# usb_host_eurorack.net
KiCad netlist of a schematic drawn in EAGLE
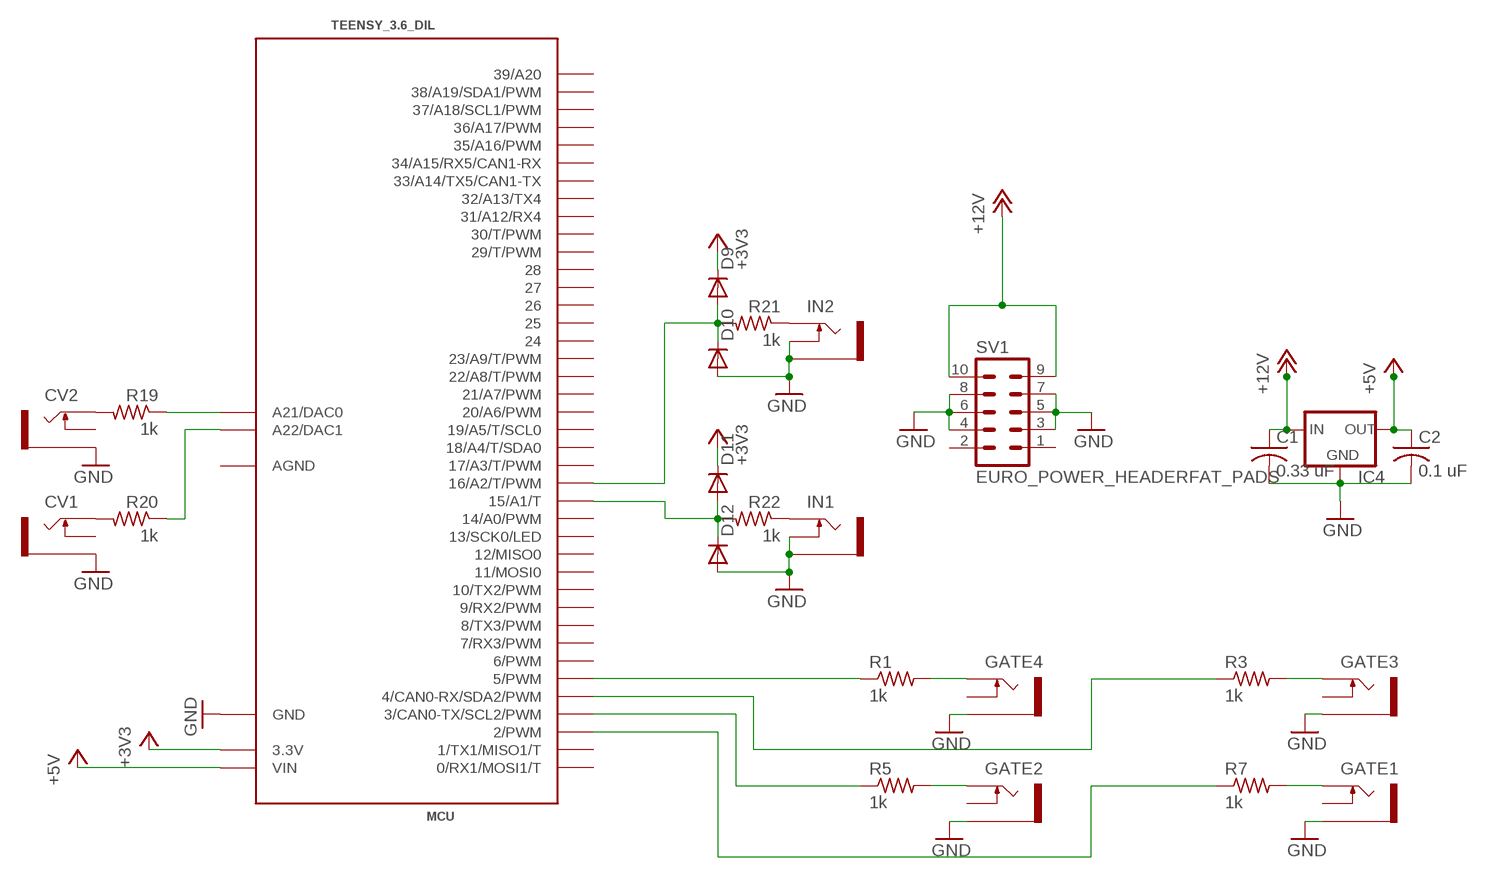
[diagram p0: schematic, sheet 1]

(export (version "E")
  (design (tool "Eeschema 10.0.6"))
  (components
    (comp (ref "C1")
      (value "0.33 uF")
      (footprint "eagle-import:C025-030X050")
      (libsource (lib "eagle-import") (part "C-US025-030X050"))
    )
    (comp (ref "C2")
      (value "0.1 uF")
      (footprint "eagle-import:C025-030X050")
      (libsource (lib "eagle-import") (part "C-US025-030X050"))
    )
    (comp (ref "CV1")
      (value "PJ302M")
      (footprint "eagle-import:PJ302M")
      (libsource (lib "eagle-import") (part "PJ302M"))
    )
    (comp (ref "CV2")
      (value "PJ302M")
      (footprint "eagle-import:PJ302M")
      (libsource (lib "eagle-import") (part "PJ302M"))
    )
    (comp (ref "D9")
      (value "SMALL_DIODEDO35-7")
      (footprint "eagle-import:DO35-7")
      (libsource (lib "eagle-import") (part "SMALL_DIODEDO35-7"))
    )
    (comp (ref "D10")
      (value "SMALL_DIODEDO35-7")
      (footprint "eagle-import:DO35-7")
      (libsource (lib "eagle-import") (part "SMALL_DIODEDO35-7"))
    )
    (comp (ref "D11")
      (value "SMALL_DIODEDO35-7")
      (footprint "eagle-import:DO35-7")
      (libsource (lib "eagle-import") (part "SMALL_DIODEDO35-7"))
    )
    (comp (ref "D12")
      (value "SMALL_DIODEDO35-7")
      (footprint "eagle-import:DO35-7")
      (libsource (lib "eagle-import") (part "SMALL_DIODEDO35-7"))
    )
    (comp (ref "GATE1")
      (value "PJ302M")
      (footprint "eagle-import:PJ302M")
      (libsource (lib "eagle-import") (part "PJ302M"))
    )
    (comp (ref "GATE2")
      (value "PJ302M")
      (footprint "eagle-import:PJ302M")
      (libsource (lib "eagle-import") (part "PJ302M"))
    )
    (comp (ref "GATE3")
      (value "PJ302M")
      (footprint "eagle-import:PJ302M")
      (libsource (lib "eagle-import") (part "PJ302M"))
    )
    (comp (ref "GATE4")
      (value "PJ302M")
      (footprint "eagle-import:PJ302M")
      (libsource (lib "eagle-import") (part "PJ302M"))
    )
    (comp (ref "IC4")
      (value "78XXL")
      (footprint "eagle-import:78XXL")
      (libsource (lib "eagle-import") (part "78XXL"))
    )
    (comp (ref "IN1")
      (value "PJ302M")
      (footprint "eagle-import:PJ302M")
      (libsource (lib "eagle-import") (part "PJ302M"))
    )
    (comp (ref "IN2")
      (value "PJ302M")
      (footprint "eagle-import:PJ302M")
      (libsource (lib "eagle-import") (part "PJ302M"))
    )
    (comp (ref "MCU")
      (value "TEENSY_3.6_DIL")
      (footprint "eagle-import:TEENSY_3.6_DIL")
      (libsource (lib "eagle-import") (part "TEENSY_3.6_DIL"))
    )
    (comp (ref "R1")
      (value "1k")
      (footprint "eagle-import:0207_10")
      (libsource (lib "eagle-import") (part "R-US_0207/10"))
    )
    (comp (ref "R3")
      (value "1k")
      (footprint "eagle-import:0207_10")
      (libsource (lib "eagle-import") (part "R-US_0207/10"))
    )
    (comp (ref "R5")
      (value "1k")
      (footprint "eagle-import:0207_10")
      (libsource (lib "eagle-import") (part "R-US_0207/10"))
    )
    (comp (ref "R7")
      (value "1k")
      (footprint "eagle-import:0207_10")
      (libsource (lib "eagle-import") (part "R-US_0207/10"))
    )
    (comp (ref "R19")
      (value "1k")
      (footprint "eagle-import:0207_10")
      (libsource (lib "eagle-import") (part "R-US_0207/10"))
    )
    (comp (ref "R20")
      (value "1k")
      (footprint "eagle-import:0207_10")
      (libsource (lib "eagle-import") (part "R-US_0207/10"))
    )
    (comp (ref "R21")
      (value "1k")
      (footprint "eagle-import:0207_10")
      (libsource (lib "eagle-import") (part "R-US_0207/10"))
    )
    (comp (ref "R22")
      (value "1k")
      (footprint "eagle-import:0207_10")
      (libsource (lib "eagle-import") (part "R-US_0207/10"))
    )
    (comp (ref "SV1")
      (value "EURO_POWER_HEADERFAT_PADS")
      (footprint "eagle-import:EURO_PWR_HEADER_FAT")
      (libsource (lib "eagle-import") (part "EURO_POWER_HEADERFAT_PADS"))
    )
  )
  (nets
    (net (code "1") (name "+3V3") (class "Default")
      (node (ref "D11") (pin "C") (pinfunction "C_C") (pintype "passive"))
      (node (ref "D9") (pin "C") (pinfunction "C_C") (pintype "passive"))
      (node (ref "MCU") (pin "3.3V") (pinfunction "3.3V_3.3V") (pintype "power_in"))
      (node (ref "MCU") (pin "3.3V3") (pinfunction "3.3V_3.3V3") (pintype "power_in"))
    )
    (net (code "2") (name "+5V") (class "Default")
      (node (ref "C2") (pin "1") (pinfunction "1_1") (pintype "passive"))
      (node (ref "IC4") (pin "OUT") (pinfunction "OUT_OUT") (pintype "passive"))
      (node (ref "MCU") (pin "VIN") (pinfunction "VIN_VIN") (pintype "power_in"))
    )
    (net (code "3") (name "+12V") (class "Default")
      (node (ref "C1") (pin "1") (pinfunction "1_1") (pintype "passive"))
      (node (ref "IC4") (pin "IN") (pinfunction "IN_IN") (pintype "input"))
      (node (ref "SV1") (pin "10") (pinfunction "10_10") (pintype "passive"))
      (node (ref "SV1") (pin "9") (pinfunction "9_9") (pintype "passive"))
    )
    (net (code "4") (name "/AGND") (class "Default")
      (node (ref "MCU") (pin "AGND") (pinfunction "AGND_AGND") (pintype "power_in"))
    )
    (net (code "5") (name "GND") (class "Default")
      (node (ref "C1") (pin "2") (pinfunction "2_2") (pintype "passive"))
      (node (ref "C2") (pin "2") (pinfunction "2_2") (pintype "passive"))
      (node (ref "CV1") (pin "GND") (pinfunction "SLEEVE_GND") (pintype "passive"))
      (node (ref "CV2") (pin "GND") (pinfunction "SLEEVE_GND") (pintype "passive"))
      (node (ref "D10") (pin "A") (pinfunction "A_A") (pintype "passive"))
      (node (ref "D12") (pin "A") (pinfunction "A_A") (pintype "passive"))
      (node (ref "GATE1") (pin "GND") (pinfunction "SLEEVE_GND") (pintype "passive"))
      (node (ref "GATE2") (pin "GND") (pinfunction "SLEEVE_GND") (pintype "passive"))
      (node (ref "GATE3") (pin "GND") (pinfunction "SLEEVE_GND") (pintype "passive"))
      (node (ref "GATE4") (pin "GND") (pinfunction "SLEEVE_GND") (pintype "passive"))
      (node (ref "IC4") (pin "GND") (pinfunction "GND_GND") (pintype "input"))
      (node (ref "IN1") (pin "GND") (pinfunction "SLEEVE_GND") (pintype "passive"))
      (node (ref "IN1") (pin "SW") (pinfunction "SWITCH_SW") (pintype "passive"))
      (node (ref "IN2") (pin "GND") (pinfunction "SLEEVE_GND") (pintype "passive"))
      (node (ref "IN2") (pin "SW") (pinfunction "SWITCH_SW") (pintype "passive"))
      (node (ref "MCU") (pin "GND") (pinfunction "GND_GND") (pintype "power_in"))
      (node (ref "MCU") (pin "GND1") (pinfunction "GND_GND1") (pintype "power_in"))
      (node (ref "SV1") (pin "3") (pinfunction "3_3") (pintype "passive"))
      (node (ref "SV1") (pin "4") (pinfunction "4_4") (pintype "passive"))
      (node (ref "SV1") (pin "5") (pinfunction "5_5") (pintype "passive"))
      (node (ref "SV1") (pin "6") (pinfunction "6_6") (pintype "passive"))
      (node (ref "SV1") (pin "7") (pinfunction "7_7") (pintype "passive"))
      (node (ref "SV1") (pin "8") (pinfunction "8_8") (pintype "passive"))
    )
    (net (code "6") (name "Net-(CV1-PadTIP)") (class "Default")
      (node (ref "CV1") (pin "TIP") (pinfunction "TIP_TIP") (pintype "passive"))
      (node (ref "R20") (pin "2") (pinfunction "2_2") (pintype "passive"))
    )
    (net (code "7") (name "Net-(CV2-PadTIP)") (class "Default")
      (node (ref "CV2") (pin "TIP") (pinfunction "TIP_TIP") (pintype "passive"))
      (node (ref "R19") (pin "2") (pinfunction "2_2") (pintype "passive"))
    )
    (net (code "8") (name "Net-(GATE1-PadTIP)") (class "Default")
      (node (ref "GATE1") (pin "TIP") (pinfunction "TIP_TIP") (pintype "passive"))
      (node (ref "R7") (pin "2") (pinfunction "2_2") (pintype "passive"))
    )
    (net (code "9") (name "Net-(GATE2-PadTIP)") (class "Default")
      (node (ref "GATE2") (pin "TIP") (pinfunction "TIP_TIP") (pintype "passive"))
      (node (ref "R5") (pin "2") (pinfunction "2_2") (pintype "passive"))
    )
    (net (code "10") (name "Net-(GATE3-PadTIP)") (class "Default")
      (node (ref "GATE3") (pin "TIP") (pinfunction "TIP_TIP") (pintype "passive"))
      (node (ref "R3") (pin "2") (pinfunction "2_2") (pintype "passive"))
    )
    (net (code "11") (name "Net-(GATE4-PadTIP)") (class "Default")
      (node (ref "GATE4") (pin "TIP") (pinfunction "TIP_TIP") (pintype "passive"))
      (node (ref "R1") (pin "2") (pinfunction "2_2") (pintype "passive"))
    )
    (net (code "12") (name "Net-(IN1-PadTIP)") (class "Default")
      (node (ref "IN1") (pin "TIP") (pinfunction "TIP_TIP") (pintype "passive"))
      (node (ref "R22") (pin "1") (pinfunction "1_1") (pintype "passive"))
    )
    (net (code "13") (name "Net-(IN2-PadTIP)") (class "Default")
      (node (ref "IN2") (pin "TIP") (pinfunction "TIP_TIP") (pintype "passive"))
      (node (ref "R21") (pin "1") (pinfunction "1_1") (pintype "passive"))
    )
    (net (code "14") (name "Net-(MCU-2{slash}PWM)") (class "Default")
      (node (ref "MCU") (pin "2") (pinfunction "2/PWM_2") (pintype "bidirectional"))
      (node (ref "R7") (pin "1") (pinfunction "1_1") (pintype "passive"))
    )
    (net (code "15") (name "Net-(MCU-3{slash}CAN0-TX{slash}SCL2{slash}PWM)") (class "Default")
      (node (ref "MCU") (pin "3") (pinfunction "3/CAN0-TX/SCL2/PWM_3") (pintype "bidirectional"))
      (node (ref "R5") (pin "1") (pinfunction "1_1") (pintype "passive"))
    )
    (net (code "16") (name "Net-(MCU-4{slash}CAN0-RX{slash}SDA2{slash}PWM)") (class "Default")
      (node (ref "MCU") (pin "4") (pinfunction "4/CAN0-RX/SDA2/PWM_4") (pintype "bidirectional"))
      (node (ref "R3") (pin "1") (pinfunction "1_1") (pintype "passive"))
    )
    (net (code "17") (name "Net-(MCU-5{slash}PWM)") (class "Default")
      (node (ref "MCU") (pin "5") (pinfunction "5/PWM_5") (pintype "bidirectional"))
      (node (ref "R1") (pin "1") (pinfunction "1_1") (pintype "passive"))
    )
    (net (code "18") (name "Net-(MCU-15{slash}A1{slash}T)") (class "Default")
      (node (ref "D11") (pin "A") (pinfunction "A_A") (pintype "passive"))
      (node (ref "D12") (pin "C") (pinfunction "C_C") (pintype "passive"))
      (node (ref "MCU") (pin "15/A1") (pinfunction "15/A1/T_15/A1") (pintype "bidirectional"))
      (node (ref "R22") (pin "2") (pinfunction "2_2") (pintype "passive"))
    )
    (net (code "19") (name "Net-(MCU-16{slash}A2{slash}T{slash}PWM)") (class "Default")
      (node (ref "D10") (pin "C") (pinfunction "C_C") (pintype "passive"))
      (node (ref "D9") (pin "A") (pinfunction "A_A") (pintype "passive"))
      (node (ref "MCU") (pin "16/A2") (pinfunction "16/A2/T/PWM_16/A2") (pintype "bidirectional"))
      (node (ref "R21") (pin "2") (pinfunction "2_2") (pintype "passive"))
    )
    (net (code "20") (name "Net-(MCU-A21{slash}DAC0)") (class "Default")
      (node (ref "MCU") (pin "A21") (pinfunction "A21/DAC0_A21") (pintype "bidirectional"))
      (node (ref "R19") (pin "1") (pinfunction "1_1") (pintype "passive"))
    )
    (net (code "21") (name "Net-(MCU-A22{slash}DAC1)") (class "Default")
      (node (ref "MCU") (pin "A22") (pinfunction "A22/DAC1_A22") (pintype "bidirectional"))
      (node (ref "R20") (pin "1") (pinfunction "1_1") (pintype "passive"))
    )
    (net (code "22") (name "unconnected-(CV1-SWITCH-PadSW)") (class "Default")
      (node (ref "CV1") (pin "SW") (pinfunction "SWITCH_SW") (pintype "passive"))
    )
    (net (code "23") (name "unconnected-(CV2-SWITCH-PadSW)") (class "Default")
      (node (ref "CV2") (pin "SW") (pinfunction "SWITCH_SW") (pintype "passive"))
    )
    (net (code "24") (name "unconnected-(GATE1-SWITCH-PadSW)") (class "Default")
      (node (ref "GATE1") (pin "SW") (pinfunction "SWITCH_SW") (pintype "passive"))
    )
    (net (code "25") (name "unconnected-(GATE2-SWITCH-PadSW)") (class "Default")
      (node (ref "GATE2") (pin "SW") (pinfunction "SWITCH_SW") (pintype "passive"))
    )
    (net (code "26") (name "unconnected-(GATE3-SWITCH-PadSW)") (class "Default")
      (node (ref "GATE3") (pin "SW") (pinfunction "SWITCH_SW") (pintype "passive"))
    )
    (net (code "27") (name "unconnected-(GATE4-SWITCH-PadSW)") (class "Default")
      (node (ref "GATE4") (pin "SW") (pinfunction "SWITCH_SW") (pintype "passive"))
    )
    (net (code "28") (name "unconnected-(MCU-0{slash}RX1{slash}MOSI1{slash}T-Pad0)") (class "Default")
      (node (ref "MCU") (pin "0") (pinfunction "0/RX1/MOSI1/T_0") (pintype "bidirectional"))
    )
    (net (code "29") (name "unconnected-(MCU-1{slash}TX1{slash}MISO1{slash}T-Pad1)") (class "Default")
      (node (ref "MCU") (pin "1") (pinfunction "1/TX1/MISO1/T_1") (pintype "bidirectional"))
    )
    (net (code "30") (name "unconnected-(MCU-6{slash}PWM-Pad6)") (class "Default")
      (node (ref "MCU") (pin "6") (pinfunction "6/PWM_6") (pintype "bidirectional"))
    )
    (net (code "31") (name "unconnected-(MCU-7{slash}RX3{slash}PWM-Pad7)") (class "Default")
      (node (ref "MCU") (pin "7") (pinfunction "7/RX3/PWM_7") (pintype "bidirectional"))
    )
    (net (code "32") (name "unconnected-(MCU-8{slash}TX3{slash}PWM-Pad8)") (class "Default")
      (node (ref "MCU") (pin "8") (pinfunction "8/TX3/PWM_8") (pintype "bidirectional"))
    )
    (net (code "33") (name "unconnected-(MCU-9{slash}RX2{slash}PWM-Pad9)") (class "Default")
      (node (ref "MCU") (pin "9") (pinfunction "9/RX2/PWM_9") (pintype "bidirectional"))
    )
    (net (code "34") (name "unconnected-(MCU-10{slash}TX2{slash}PWM-Pad10)") (class "Default")
      (node (ref "MCU") (pin "10") (pinfunction "10/TX2/PWM_10") (pintype "bidirectional"))
    )
    (net (code "35") (name "unconnected-(MCU-11{slash}MOSI0-Pad11)") (class "Default")
      (node (ref "MCU") (pin "11") (pinfunction "11/MOSI0_11") (pintype "bidirectional"))
    )
    (net (code "36") (name "unconnected-(MCU-12{slash}MISO0-Pad12)") (class "Default")
      (node (ref "MCU") (pin "12") (pinfunction "12/MISO0_12") (pintype "bidirectional"))
    )
    (net (code "37") (name "unconnected-(MCU-13{slash}SCK0{slash}LED-Pad13)") (class "Default")
      (node (ref "MCU") (pin "13") (pinfunction "13/SCK0/LED_13") (pintype "bidirectional"))
    )
    (net (code "38") (name "unconnected-(MCU-14{slash}A0{slash}PWM-Pad14{slash}A0)") (class "Default")
      (node (ref "MCU") (pin "14/A0") (pinfunction "14/A0/PWM_14/A0") (pintype "bidirectional"))
    )
    (net (code "39") (name "unconnected-(MCU-17{slash}A3{slash}T{slash}PWM-Pad17{slash}A3)") (class "Default")
      (node (ref "MCU") (pin "17/A3") (pinfunction "17/A3/T/PWM_17/A3") (pintype "bidirectional"))
    )
    (net (code "40") (name "unconnected-(MCU-18{slash}A4{slash}T{slash}SDA0-Pad18{slash}A4)") (class "Default")
      (node (ref "MCU") (pin "18/A4") (pinfunction "18/A4/T/SDA0_18/A4") (pintype "bidirectional"))
    )
    (net (code "41") (name "unconnected-(MCU-19{slash}A5{slash}T{slash}SCL0-Pad19{slash}A5)") (class "Default")
      (node (ref "MCU") (pin "19/A5") (pinfunction "19/A5/T/SCL0_19/A5") (pintype "bidirectional"))
    )
    (net (code "42") (name "unconnected-(MCU-20{slash}A6{slash}PWM-Pad20{slash}A6)") (class "Default")
      (node (ref "MCU") (pin "20/A6") (pinfunction "20/A6/PWM_20/A6") (pintype "bidirectional"))
    )
    (net (code "43") (name "unconnected-(MCU-21{slash}A7{slash}PWM-Pad21{slash}A7)") (class "Default")
      (node (ref "MCU") (pin "21/A7") (pinfunction "21/A7/PWM_21/A7") (pintype "bidirectional"))
    )
    (net (code "44") (name "unconnected-(MCU-22{slash}A8{slash}T{slash}PWM-Pad22{slash}A8)") (class "Default")
      (node (ref "MCU") (pin "22/A8") (pinfunction "22/A8/T/PWM_22/A8") (pintype "bidirectional"))
    )
    (net (code "45") (name "unconnected-(MCU-23{slash}A9{slash}T{slash}PWM-Pad23{slash}A9)") (class "Default")
      (node (ref "MCU") (pin "23/A9") (pinfunction "23/A9/T/PWM_23/A9") (pintype "bidirectional"))
    )
    (net (code "46") (name "unconnected-(MCU-29{slash}T{slash}PWM-Pad29)") (class "Default")
      (node (ref "MCU") (pin "29") (pinfunction "29/T/PWM_29") (pintype "bidirectional"))
    )
    (net (code "47") (name "unconnected-(MCU-30{slash}T{slash}PWM-Pad30)") (class "Default")
      (node (ref "MCU") (pin "30") (pinfunction "30/T/PWM_30") (pintype "bidirectional"))
    )
    (net (code "48") (name "unconnected-(MCU-31{slash}A12{slash}RX4-Pad31{slash}A12)") (class "Default")
      (node (ref "MCU") (pin "31/A12") (pinfunction "31/A12/RX4_31/A12") (pintype "bidirectional"))
    )
    (net (code "49") (name "unconnected-(MCU-32{slash}A13{slash}TX4-Pad32{slash}A13)") (class "Default")
      (node (ref "MCU") (pin "32/A13") (pinfunction "32/A13/TX4_32/A13") (pintype "bidirectional"))
    )
    (net (code "50") (name "unconnected-(MCU-33{slash}A14{slash}TX5{slash}CAN1-TX-Pad33{slash}A14)") (class "Default")
      (node (ref "MCU") (pin "33/A14") (pinfunction "33/A14/TX5/CAN1-TX_33/A14") (pintype "bidirectional"))
    )
    (net (code "51") (name "unconnected-(MCU-34{slash}A15{slash}RX5{slash}CAN1-RX-Pad34{slash}A15)") (class "Default")
      (node (ref "MCU") (pin "34/A15") (pinfunction "34/A15/RX5/CAN1-RX_34/A15") (pintype "bidirectional"))
    )
    (net (code "52") (name "unconnected-(MCU-35{slash}A16{slash}PWM-Pad35{slash}A16)") (class "Default")
      (node (ref "MCU") (pin "35/A16") (pinfunction "35/A16/PWM_35/A16") (pintype "bidirectional"))
    )
    (net (code "53") (name "unconnected-(MCU-36{slash}A17{slash}PWM-Pad36{slash}A17)") (class "Default")
      (node (ref "MCU") (pin "36/A17") (pinfunction "36/A17/PWM_36/A17") (pintype "bidirectional"))
    )
    (net (code "54") (name "unconnected-(MCU-37{slash}A18{slash}SCL1{slash}PWM-Pad37{slash}A18)") (class "Default")
      (node (ref "MCU") (pin "37/A18") (pinfunction "37/A18/SCL1/PWM_37/A18") (pintype "bidirectional"))
    )
    (net (code "55") (name "unconnected-(MCU-38{slash}A19{slash}SDA1{slash}PWM-Pad38{slash}A19)") (class "Default")
      (node (ref "MCU") (pin "38/A19") (pinfunction "38/A19/SDA1/PWM_38/A19") (pintype "bidirectional"))
    )
    (net (code "56") (name "unconnected-(MCU-Pad24)") (class "Default")
      (node (ref "MCU") (pin "24") (pinfunction "24_24") (pintype "bidirectional"))
    )
    (net (code "57") (name "unconnected-(MCU-Pad25)") (class "Default")
      (node (ref "MCU") (pin "25") (pinfunction "25_25") (pintype "bidirectional"))
    )
    (net (code "58") (name "unconnected-(MCU-Pad26)") (class "Default")
      (node (ref "MCU") (pin "26") (pinfunction "26_26") (pintype "bidirectional"))
    )
    (net (code "59") (name "unconnected-(MCU-Pad27)") (class "Default")
      (node (ref "MCU") (pin "27") (pinfunction "27_27") (pintype "bidirectional"))
    )
    (net (code "60") (name "unconnected-(MCU-Pad28)") (class "Default")
      (node (ref "MCU") (pin "28") (pinfunction "28_28") (pintype "bidirectional"))
    )
    (net (code "61") (name "unconnected-(MCU-Pad39{slash}A20)") (class "Default")
      (node (ref "MCU") (pin "39/A20") (pinfunction "39/A20_39/A20") (pintype "bidirectional"))
    )
    (net (code "62") (name "unconnected-(SV1-Pad1)") (class "Default")
      (node (ref "SV1") (pin "1") (pinfunction "1_1") (pintype "passive"))
    )
    (net (code "63") (name "unconnected-(SV1-Pad2)") (class "Default")
      (node (ref "SV1") (pin "2") (pinfunction "2_2") (pintype "passive"))
    )
  )
)
